# bmsMaster_usb.net
KiCad netlist of a schematic drawn in Altium Designer
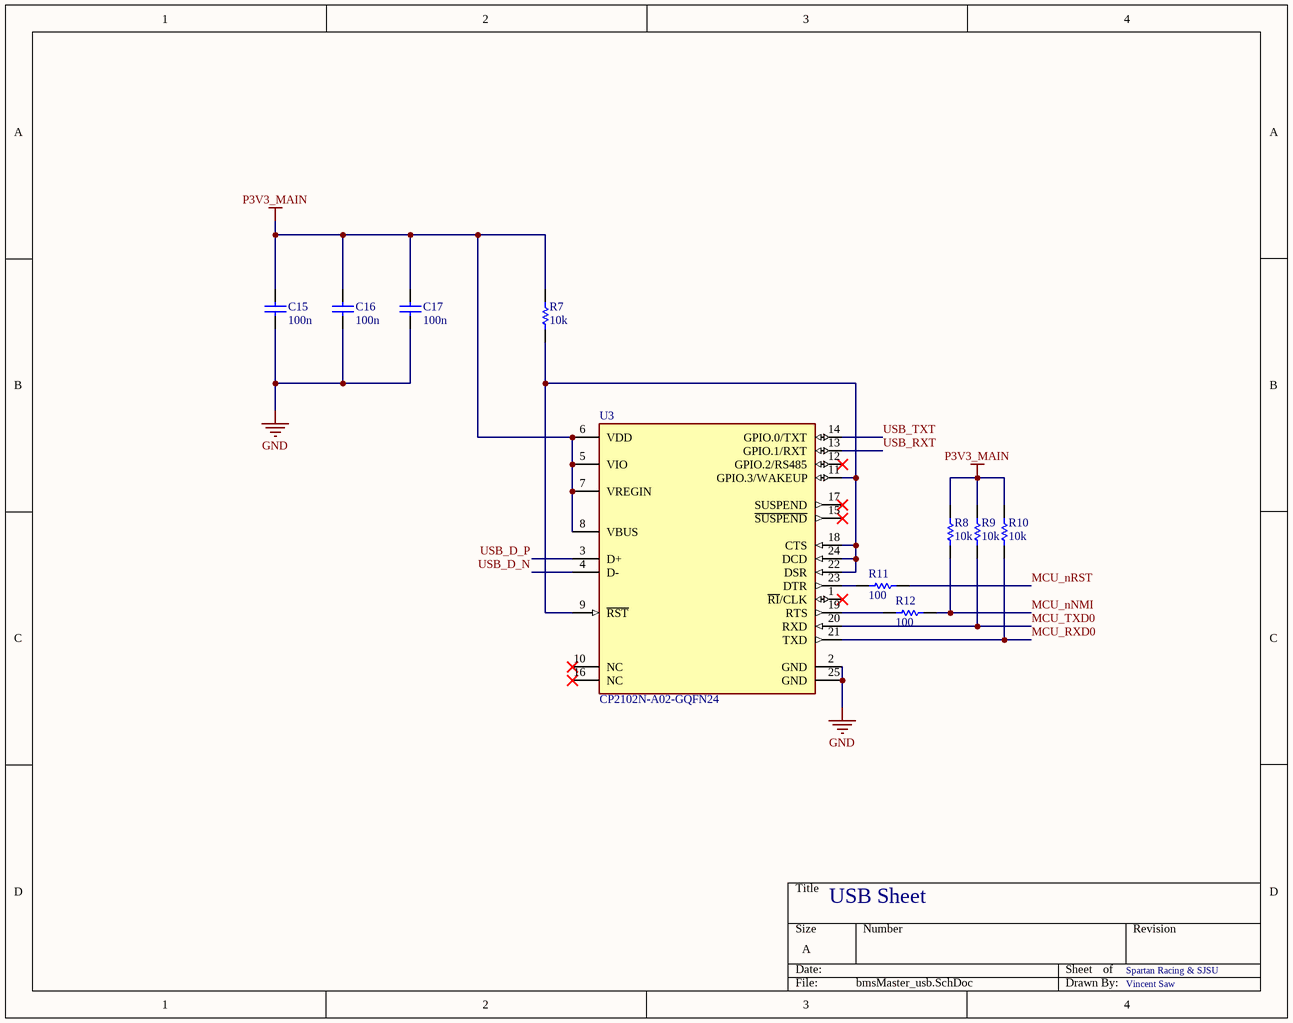
[diagram p0: bmsMaster_usb.SchDoc]

(export (version "E")
  (design (tool "Eeschema 10.0.6"))
  (components
    (comp (ref "C15")
      (value "100n")
      (description "Capacitor")
      (libsource (lib "Simulation Generic Components") (part "Capacitor"))
    )
    (comp (ref "C16")
      (value "100n")
      (description "Capacitor")
      (libsource (lib "Simulation Generic Components") (part "Capacitor"))
    )
    (comp (ref "C17")
      (value "100n")
      (description "Capacitor")
      (libsource (lib "Simulation Generic Components") (part "Capacitor"))
    )
    (comp (ref "R7")
      (value "10k")
      (description "Resistor")
      (libsource (lib "Simulation Generic Components") (part "Resistor"))
    )
    (comp (ref "R8")
      (value "10k")
      (description "Resistor")
      (libsource (lib "Simulation Generic Components") (part "Resistor"))
    )
    (comp (ref "R9")
      (value "10k")
      (description "Resistor")
      (libsource (lib "Simulation Generic Components") (part "Resistor"))
    )
    (comp (ref "R10")
      (value "10k")
      (description "Resistor")
      (libsource (lib "Simulation Generic Components") (part "Resistor"))
    )
    (comp (ref "R11")
      (value "100")
      (description "Resistor")
      (libsource (lib "Simulation Generic Components") (part "Resistor"))
    )
    (comp (ref "R12")
      (value "100")
      (description "Resistor")
      (libsource (lib "Simulation Generic Components") (part "Resistor"))
    )
    (comp (ref "U3")
      (value "CP2102N-A02-GQFN24")
      (footprint "FP-CP2102N-A02-GQFN24-MFG")
      (description "IC USB TO UART BRIDGE QFN24")
      (libsource (lib "Altium Content Vault") (part "132705adcabca70c0fc25feb25b66a0"))
    )
  )
  (nets
    (net (code "1") (name "/MCU_RXD0") (class "Default")
      (node (ref "R10") (pin "1") (pinfunction "1_1") (pintype "passive"))
      (node (ref "U3") (pin "21") (pinfunction "TXD_21") (pintype "output"))
    )
    (net (code "2") (name "/MCU_TXD0") (class "Default")
      (node (ref "R9") (pin "1") (pinfunction "1_1") (pintype "passive"))
      (node (ref "U3") (pin "20") (pinfunction "RXD_20") (pintype "input"))
    )
    (net (code "3") (name "/MCU_nNMI") (class "Default")
      (node (ref "R12") (pin "1") (pinfunction "1_1") (pintype "passive"))
      (node (ref "R8") (pin "1") (pinfunction "1_1") (pintype "passive"))
    )
    (net (code "4") (name "/MCU_nRST") (class "Default")
      (node (ref "R11") (pin "1") (pinfunction "1_1") (pintype "passive"))
    )
    (net (code "5") (name "/USB_D_N") (class "Default")
      (node (ref "U3") (pin "4") (pinfunction "D-_4") (pintype "passive"))
    )
    (net (code "6") (name "/USB_D_P") (class "Default")
      (node (ref "U3") (pin "3") (pinfunction "D+_3") (pintype "passive"))
    )
    (net (code "7") (name "/USB_RXT") (class "Default")
      (node (ref "U3") (pin "13") (pinfunction "GPIO.1/RXT_13") (pintype "bidirectional"))
    )
    (net (code "8") (name "/USB_TXT") (class "Default")
      (node (ref "U3") (pin "14") (pinfunction "GPIO.0/TXT_14") (pintype "bidirectional"))
    )
    (net (code "9") (name "GND") (class "Default")
      (node (ref "C15") (pin "1") (pinfunction "1_1") (pintype "passive"))
      (node (ref "C16") (pin "1") (pinfunction "1_1") (pintype "passive"))
      (node (ref "C17") (pin "1") (pinfunction "1_1") (pintype "passive"))
      (node (ref "U3") (pin "2") (pinfunction "GND_2") (pintype "power_in"))
      (node (ref "U3") (pin "25") (pinfunction "GND_25") (pintype "power_in"))
    )
    (net (code "10") (name "Net-(U3-CTS)") (class "Default")
      (node (ref "R7") (pin "1") (pinfunction "1_1") (pintype "passive"))
      (node (ref "U3") (pin "11") (pinfunction "GPIO.3/WAKEUP_11") (pintype "bidirectional"))
      (node (ref "U3") (pin "18") (pinfunction "CTS_18") (pintype "input"))
      (node (ref "U3") (pin "22") (pinfunction "DSR_22") (pintype "input"))
      (node (ref "U3") (pin "24") (pinfunction "DCD_24") (pintype "input"))
      (node (ref "U3") (pin "9") (pinfunction "~{RST}_9") (pintype "input"))
    )
    (net (code "11") (name "Net-(U3-DTR)") (class "Default")
      (node (ref "R11") (pin "2") (pinfunction "2_2") (pintype "passive"))
      (node (ref "U3") (pin "23") (pinfunction "DTR_23") (pintype "output"))
    )
    (net (code "12") (name "Net-(U3-RTS)") (class "Default")
      (node (ref "R12") (pin "2") (pinfunction "2_2") (pintype "passive"))
      (node (ref "U3") (pin "19") (pinfunction "RTS_19") (pintype "output"))
    )
    (net (code "13") (name "P3V3_MAIN") (class "Default")
      (node (ref "C15") (pin "2") (pinfunction "2_2") (pintype "passive"))
      (node (ref "C16") (pin "2") (pinfunction "2_2") (pintype "passive"))
      (node (ref "C17") (pin "2") (pinfunction "2_2") (pintype "passive"))
      (node (ref "R10") (pin "2") (pinfunction "2_2") (pintype "passive"))
      (node (ref "R7") (pin "2") (pinfunction "2_2") (pintype "passive"))
      (node (ref "R8") (pin "2") (pinfunction "2_2") (pintype "passive"))
      (node (ref "R9") (pin "2") (pinfunction "2_2") (pintype "passive"))
      (node (ref "U3") (pin "5") (pinfunction "VIO_5") (pintype "power_in"))
      (node (ref "U3") (pin "6") (pinfunction "VDD_6") (pintype "power_in"))
      (node (ref "U3") (pin "7") (pinfunction "VREGIN_7") (pintype "power_in"))
      (node (ref "U3") (pin "8") (pinfunction "VBUS_8") (pintype "power_in"))
    )
    (net (code "14") (name "unconnected-(U3-GPIO.2{slash}RS485-Pad12)") (class "Default")
      (node (ref "U3") (pin "12") (pinfunction "GPIO.2/RS485_12") (pintype "bidirectional+no_connect"))
    )
    (net (code "15") (name "unconnected-(U3-NC-Pad10)") (class "Default")
      (node (ref "U3") (pin "10") (pinfunction "NC_10") (pintype "passive+no_connect"))
    )
    (net (code "16") (name "unconnected-(U3-NC-Pad16)") (class "Default")
      (node (ref "U3") (pin "16") (pinfunction "NC_16") (pintype "passive+no_connect"))
    )
    (net (code "17") (name "unconnected-(U3-SUSPEND-Pad17)") (class "Default")
      (node (ref "U3") (pin "17") (pinfunction "SUSPEND_17") (pintype "output+no_connect"))
    )
    (net (code "18") (name "unconnected-(U3-~{RI}{slash}CLK-Pad1)") (class "Default")
      (node (ref "U3") (pin "1") (pinfunction "~{RI}/CLK_1") (pintype "bidirectional+no_connect"))
    )
    (net (code "19") (name "unconnected-(U3-~{SUSPEND}-Pad15)") (class "Default")
      (node (ref "U3") (pin "15") (pinfunction "~{SUSPEND}_15") (pintype "output+no_connect"))
    )
  )
)
